# Chess_Clock_Front_Display_SCH.net
KiCad netlist of a schematic drawn in Altium Designer
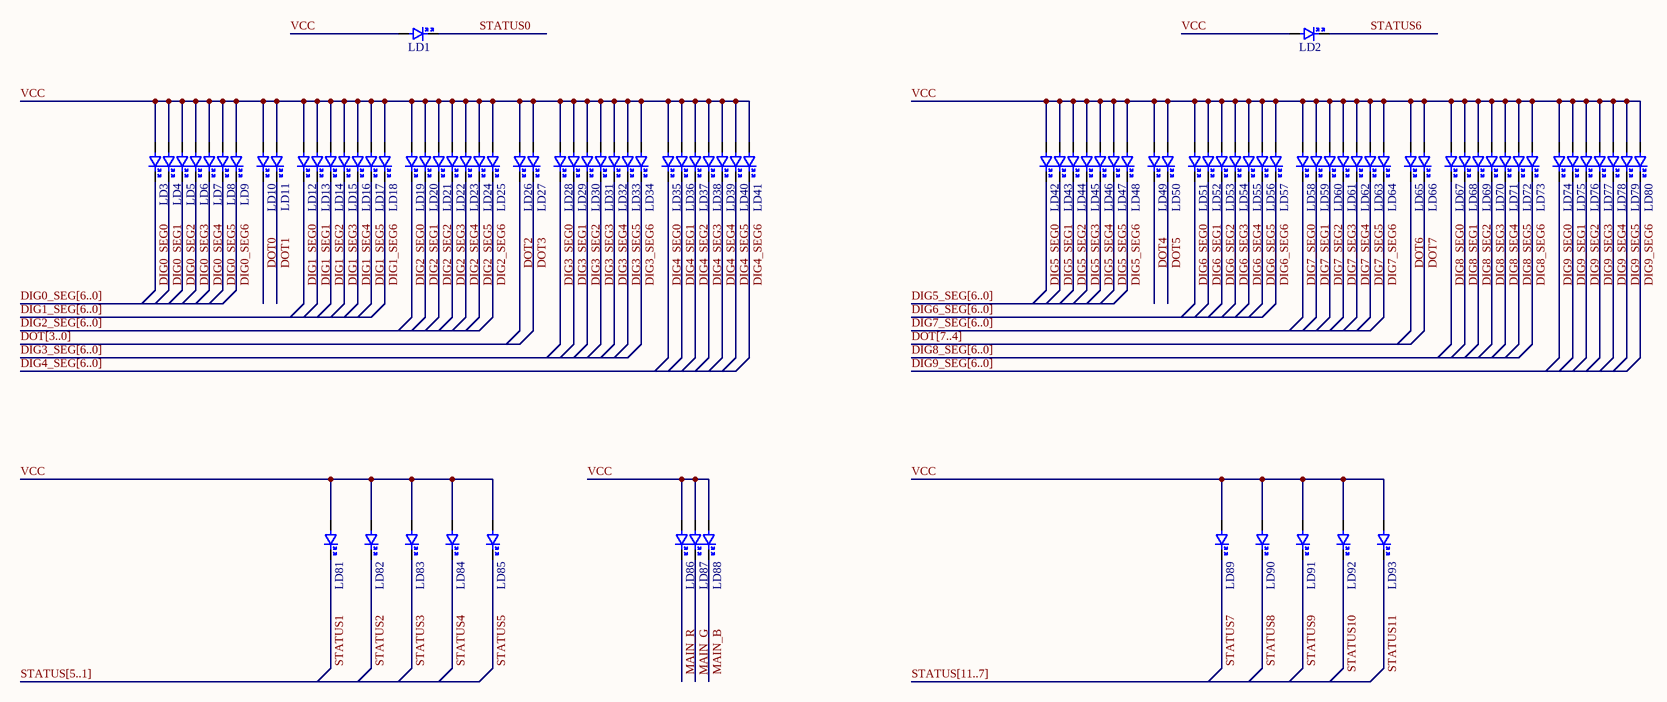
[diagram p0: Chess Clock Front Display SCH.SchDoc]

(export (version "E")
  (design (tool "Eeschema 10.0.6"))
  (components
    (comp (ref "LD1")
      (value "LED 0603")
      (footprint "LED 0603")
      (libsource (lib "Chess Clock Front Display") (part "LED 0603"))
    )
    (comp (ref "LD2")
      (value "LED 0603")
      (footprint "LED 0603")
      (libsource (lib "Chess Clock Front Display") (part "LED 0603"))
    )
    (comp (ref "LD3")
      (value "LED 0603")
      (footprint "LED 0603")
      (libsource (lib "Chess Clock Front Display") (part "LED 0603"))
    )
    (comp (ref "LD4")
      (value "LED 0603")
      (footprint "LED 0603")
      (libsource (lib "Chess Clock Front Display") (part "LED 0603"))
    )
    (comp (ref "LD5")
      (value "LED 0603")
      (footprint "LED 0603")
      (libsource (lib "Chess Clock Front Display") (part "LED 0603"))
    )
    (comp (ref "LD6")
      (value "LED 0603")
      (footprint "LED 0603")
      (libsource (lib "Chess Clock Front Display") (part "LED 0603"))
    )
    (comp (ref "LD7")
      (value "LED 0603")
      (footprint "LED 0603")
      (libsource (lib "Chess Clock Front Display") (part "LED 0603"))
    )
    (comp (ref "LD8")
      (value "LED 0603")
      (footprint "LED 0603")
      (libsource (lib "Chess Clock Front Display") (part "LED 0603"))
    )
    (comp (ref "LD9")
      (value "LED 0603")
      (footprint "LED 0603")
      (libsource (lib "Chess Clock Front Display") (part "LED 0603"))
    )
    (comp (ref "LD10")
      (value "LED 0603")
      (footprint "LED 0603")
      (libsource (lib "Chess Clock Front Display") (part "LED 0603"))
    )
    (comp (ref "LD11")
      (value "LED 0603")
      (footprint "LED 0603")
      (libsource (lib "Chess Clock Front Display") (part "LED 0603"))
    )
    (comp (ref "LD12")
      (value "LED 0603")
      (footprint "LED 0603")
      (libsource (lib "Chess Clock Front Display") (part "LED 0603"))
    )
    (comp (ref "LD13")
      (value "LED 0603")
      (footprint "LED 0603")
      (libsource (lib "Chess Clock Front Display") (part "LED 0603"))
    )
    (comp (ref "LD14")
      (value "LED 0603")
      (footprint "LED 0603")
      (libsource (lib "Chess Clock Front Display") (part "LED 0603"))
    )
    (comp (ref "LD15")
      (value "LED 0603")
      (footprint "LED 0603")
      (libsource (lib "Chess Clock Front Display") (part "LED 0603"))
    )
    (comp (ref "LD16")
      (value "LED 0603")
      (footprint "LED 0603")
      (libsource (lib "Chess Clock Front Display") (part "LED 0603"))
    )
    (comp (ref "LD17")
      (value "LED 0603")
      (footprint "LED 0603")
      (libsource (lib "Chess Clock Front Display") (part "LED 0603"))
    )
    (comp (ref "LD18")
      (value "LED 0603")
      (footprint "LED 0603")
      (libsource (lib "Chess Clock Front Display") (part "LED 0603"))
    )
    (comp (ref "LD19")
      (value "LED 0603")
      (footprint "LED 0603")
      (libsource (lib "Chess Clock Front Display") (part "LED 0603"))
    )
    (comp (ref "LD20")
      (value "LED 0603")
      (footprint "LED 0603")
      (libsource (lib "Chess Clock Front Display") (part "LED 0603"))
    )
    (comp (ref "LD21")
      (value "LED 0603")
      (footprint "LED 0603")
      (libsource (lib "Chess Clock Front Display") (part "LED 0603"))
    )
    (comp (ref "LD22")
      (value "LED 0603")
      (footprint "LED 0603")
      (libsource (lib "Chess Clock Front Display") (part "LED 0603"))
    )
    (comp (ref "LD23")
      (value "LED 0603")
      (footprint "LED 0603")
      (libsource (lib "Chess Clock Front Display") (part "LED 0603"))
    )
    (comp (ref "LD24")
      (value "LED 0603")
      (footprint "LED 0603")
      (libsource (lib "Chess Clock Front Display") (part "LED 0603"))
    )
    (comp (ref "LD25")
      (value "LED 0603")
      (footprint "LED 0603")
      (libsource (lib "Chess Clock Front Display") (part "LED 0603"))
    )
    (comp (ref "LD26")
      (value "LED 0603")
      (footprint "LED 0603")
      (libsource (lib "Chess Clock Front Display") (part "LED 0603"))
    )
    (comp (ref "LD27")
      (value "LED 0603")
      (footprint "LED 0603")
      (libsource (lib "Chess Clock Front Display") (part "LED 0603"))
    )
    (comp (ref "LD28")
      (value "LED 0603")
      (footprint "LED 0603")
      (libsource (lib "Chess Clock Front Display") (part "LED 0603"))
    )
    (comp (ref "LD29")
      (value "LED 0603")
      (footprint "LED 0603")
      (libsource (lib "Chess Clock Front Display") (part "LED 0603"))
    )
    (comp (ref "LD30")
      (value "LED 0603")
      (footprint "LED 0603")
      (libsource (lib "Chess Clock Front Display") (part "LED 0603"))
    )
    (comp (ref "LD31")
      (value "LED 0603")
      (footprint "LED 0603")
      (libsource (lib "Chess Clock Front Display") (part "LED 0603"))
    )
    (comp (ref "LD32")
      (value "LED 0603")
      (footprint "LED 0603")
      (libsource (lib "Chess Clock Front Display") (part "LED 0603"))
    )
    (comp (ref "LD33")
      (value "LED 0603")
      (footprint "LED 0603")
      (libsource (lib "Chess Clock Front Display") (part "LED 0603"))
    )
    (comp (ref "LD34")
      (value "LED 0603")
      (footprint "LED 0603")
      (libsource (lib "Chess Clock Front Display") (part "LED 0603"))
    )
    (comp (ref "LD35")
      (value "LED 0603")
      (footprint "LED 0603")
      (libsource (lib "Chess Clock Front Display") (part "LED 0603"))
    )
    (comp (ref "LD36")
      (value "LED 0603")
      (footprint "LED 0603")
      (libsource (lib "Chess Clock Front Display") (part "LED 0603"))
    )
    (comp (ref "LD37")
      (value "LED 0603")
      (footprint "LED 0603")
      (libsource (lib "Chess Clock Front Display") (part "LED 0603"))
    )
    (comp (ref "LD38")
      (value "LED 0603")
      (footprint "LED 0603")
      (libsource (lib "Chess Clock Front Display") (part "LED 0603"))
    )
    (comp (ref "LD39")
      (value "LED 0603")
      (footprint "LED 0603")
      (libsource (lib "Chess Clock Front Display") (part "LED 0603"))
    )
    (comp (ref "LD40")
      (value "LED 0603")
      (footprint "LED 0603")
      (libsource (lib "Chess Clock Front Display") (part "LED 0603"))
    )
    (comp (ref "LD41")
      (value "LED 0603")
      (footprint "LED 0603")
      (libsource (lib "Chess Clock Front Display") (part "LED 0603"))
    )
    (comp (ref "LD42")
      (value "LED 0603")
      (footprint "LED 0603")
      (libsource (lib "Chess Clock Front Display") (part "LED 0603"))
    )
    (comp (ref "LD43")
      (value "LED 0603")
      (footprint "LED 0603")
      (libsource (lib "Chess Clock Front Display") (part "LED 0603"))
    )
    (comp (ref "LD44")
      (value "LED 0603")
      (footprint "LED 0603")
      (libsource (lib "Chess Clock Front Display") (part "LED 0603"))
    )
    (comp (ref "LD45")
      (value "LED 0603")
      (footprint "LED 0603")
      (libsource (lib "Chess Clock Front Display") (part "LED 0603"))
    )
    (comp (ref "LD46")
      (value "LED 0603")
      (footprint "LED 0603")
      (libsource (lib "Chess Clock Front Display") (part "LED 0603"))
    )
    (comp (ref "LD47")
      (value "LED 0603")
      (footprint "LED 0603")
      (libsource (lib "Chess Clock Front Display") (part "LED 0603"))
    )
    (comp (ref "LD48")
      (value "LED 0603")
      (footprint "LED 0603")
      (libsource (lib "Chess Clock Front Display") (part "LED 0603"))
    )
    (comp (ref "LD49")
      (value "LED 0603")
      (footprint "LED 0603")
      (libsource (lib "Chess Clock Front Display") (part "LED 0603"))
    )
    (comp (ref "LD50")
      (value "LED 0603")
      (footprint "LED 0603")
      (libsource (lib "Chess Clock Front Display") (part "LED 0603"))
    )
    (comp (ref "LD51")
      (value "LED 0603")
      (footprint "LED 0603")
      (libsource (lib "Chess Clock Front Display") (part "LED 0603"))
    )
    (comp (ref "LD52")
      (value "LED 0603")
      (footprint "LED 0603")
      (libsource (lib "Chess Clock Front Display") (part "LED 0603"))
    )
    (comp (ref "LD53")
      (value "LED 0603")
      (footprint "LED 0603")
      (libsource (lib "Chess Clock Front Display") (part "LED 0603"))
    )
    (comp (ref "LD54")
      (value "LED 0603")
      (footprint "LED 0603")
      (libsource (lib "Chess Clock Front Display") (part "LED 0603"))
    )
    (comp (ref "LD55")
      (value "LED 0603")
      (footprint "LED 0603")
      (libsource (lib "Chess Clock Front Display") (part "LED 0603"))
    )
    (comp (ref "LD56")
      (value "LED 0603")
      (footprint "LED 0603")
      (libsource (lib "Chess Clock Front Display") (part "LED 0603"))
    )
    (comp (ref "LD57")
      (value "LED 0603")
      (footprint "LED 0603")
      (libsource (lib "Chess Clock Front Display") (part "LED 0603"))
    )
    (comp (ref "LD58")
      (value "LED 0603")
      (footprint "LED 0603")
      (libsource (lib "Chess Clock Front Display") (part "LED 0603"))
    )
    (comp (ref "LD59")
      (value "LED 0603")
      (footprint "LED 0603")
      (libsource (lib "Chess Clock Front Display") (part "LED 0603"))
    )
    (comp (ref "LD60")
      (value "LED 0603")
      (footprint "LED 0603")
      (libsource (lib "Chess Clock Front Display") (part "LED 0603"))
    )
    (comp (ref "LD61")
      (value "LED 0603")
      (footprint "LED 0603")
      (libsource (lib "Chess Clock Front Display") (part "LED 0603"))
    )
    (comp (ref "LD62")
      (value "LED 0603")
      (footprint "LED 0603")
      (libsource (lib "Chess Clock Front Display") (part "LED 0603"))
    )
    (comp (ref "LD63")
      (value "LED 0603")
      (footprint "LED 0603")
      (libsource (lib "Chess Clock Front Display") (part "LED 0603"))
    )
    (comp (ref "LD64")
      (value "LED 0603")
      (footprint "LED 0603")
      (libsource (lib "Chess Clock Front Display") (part "LED 0603"))
    )
    (comp (ref "LD65")
      (value "LED 0603")
      (footprint "LED 0603")
      (libsource (lib "Chess Clock Front Display") (part "LED 0603"))
    )
    (comp (ref "LD66")
      (value "LED 0603")
      (footprint "LED 0603")
      (libsource (lib "Chess Clock Front Display") (part "LED 0603"))
    )
    (comp (ref "LD67")
      (value "LED 0603")
      (footprint "LED 0603")
      (libsource (lib "Chess Clock Front Display") (part "LED 0603"))
    )
    (comp (ref "LD68")
      (value "LED 0603")
      (footprint "LED 0603")
      (libsource (lib "Chess Clock Front Display") (part "LED 0603"))
    )
    (comp (ref "LD69")
      (value "LED 0603")
      (footprint "LED 0603")
      (libsource (lib "Chess Clock Front Display") (part "LED 0603"))
    )
    (comp (ref "LD70")
      (value "LED 0603")
      (footprint "LED 0603")
      (libsource (lib "Chess Clock Front Display") (part "LED 0603"))
    )
    (comp (ref "LD71")
      (value "LED 0603")
      (footprint "LED 0603")
      (libsource (lib "Chess Clock Front Display") (part "LED 0603"))
    )
    (comp (ref "LD72")
      (value "LED 0603")
      (footprint "LED 0603")
      (libsource (lib "Chess Clock Front Display") (part "LED 0603"))
    )
    (comp (ref "LD73")
      (value "LED 0603")
      (footprint "LED 0603")
      (libsource (lib "Chess Clock Front Display") (part "LED 0603"))
    )
    (comp (ref "LD74")
      (value "LED 0603")
      (footprint "LED 0603")
      (libsource (lib "Chess Clock Front Display") (part "LED 0603"))
    )
    (comp (ref "LD75")
      (value "LED 0603")
      (footprint "LED 0603")
      (libsource (lib "Chess Clock Front Display") (part "LED 0603"))
    )
    (comp (ref "LD76")
      (value "LED 0603")
      (footprint "LED 0603")
      (libsource (lib "Chess Clock Front Display") (part "LED 0603"))
    )
    (comp (ref "LD77")
      (value "LED 0603")
      (footprint "LED 0603")
      (libsource (lib "Chess Clock Front Display") (part "LED 0603"))
    )
    (comp (ref "LD78")
      (value "LED 0603")
      (footprint "LED 0603")
      (libsource (lib "Chess Clock Front Display") (part "LED 0603"))
    )
    (comp (ref "LD79")
      (value "LED 0603")
      (footprint "LED 0603")
      (libsource (lib "Chess Clock Front Display") (part "LED 0603"))
    )
    (comp (ref "LD80")
      (value "LED 0603")
      (footprint "LED 0603")
      (libsource (lib "Chess Clock Front Display") (part "LED 0603"))
    )
    (comp (ref "LD81")
      (value "LED 0603")
      (footprint "LED 0603")
      (libsource (lib "Chess Clock Front Display") (part "LED 0603"))
    )
    (comp (ref "LD82")
      (value "LED 0603")
      (footprint "LED 0603")
      (libsource (lib "Chess Clock Front Display") (part "LED 0603"))
    )
    (comp (ref "LD83")
      (value "LED 0603")
      (footprint "LED 0603")
      (libsource (lib "Chess Clock Front Display") (part "LED 0603"))
    )
    (comp (ref "LD84")
      (value "LED 0603")
      (footprint "LED 0603")
      (libsource (lib "Chess Clock Front Display") (part "LED 0603"))
    )
    (comp (ref "LD85")
      (value "LED 0603")
      (footprint "LED 0603")
      (libsource (lib "Chess Clock Front Display") (part "LED 0603"))
    )
    (comp (ref "LD86")
      (value "LED 0603")
      (footprint "LED 0603")
      (libsource (lib "Chess Clock Front Display") (part "LED 0603"))
    )
    (comp (ref "LD87")
      (value "LED 0603")
      (footprint "LED 0603")
      (libsource (lib "Chess Clock Front Display") (part "LED 0603"))
    )
    (comp (ref "LD88")
      (value "LED 0603")
      (footprint "LED 0603")
      (libsource (lib "Chess Clock Front Display") (part "LED 0603"))
    )
    (comp (ref "LD89")
      (value "LED 0603")
      (footprint "LED 0603")
      (libsource (lib "Chess Clock Front Display") (part "LED 0603"))
    )
    (comp (ref "LD90")
      (value "LED 0603")
      (footprint "LED 0603")
      (libsource (lib "Chess Clock Front Display") (part "LED 0603"))
    )
    (comp (ref "LD91")
      (value "LED 0603")
      (footprint "LED 0603")
      (libsource (lib "Chess Clock Front Display") (part "LED 0603"))
    )
    (comp (ref "LD92")
      (value "LED 0603")
      (footprint "LED 0603")
      (libsource (lib "Chess Clock Front Display") (part "LED 0603"))
    )
    (comp (ref "LD93")
      (value "LED 0603")
      (footprint "LED 0603")
      (libsource (lib "Chess Clock Front Display") (part "LED 0603"))
    )
  )
  (nets
    (net (code "1") (name "/DIG0_SEG0") (class "Default")
      (node (ref "LD3") (pin "2") (pinfunction "2_2") (pintype "passive"))
    )
    (net (code "2") (name "/DIG0_SEG1") (class "Default")
      (node (ref "LD4") (pin "2") (pinfunction "2_2") (pintype "passive"))
    )
    (net (code "3") (name "/DIG0_SEG2") (class "Default")
      (node (ref "LD5") (pin "2") (pinfunction "2_2") (pintype "passive"))
    )
    (net (code "4") (name "/DIG0_SEG3") (class "Default")
      (node (ref "LD6") (pin "2") (pinfunction "2_2") (pintype "passive"))
    )
    (net (code "5") (name "/DIG0_SEG4") (class "Default")
      (node (ref "LD7") (pin "2") (pinfunction "2_2") (pintype "passive"))
    )
    (net (code "6") (name "/DIG0_SEG5") (class "Default")
      (node (ref "LD8") (pin "2") (pinfunction "2_2") (pintype "passive"))
    )
    (net (code "7") (name "/DIG0_SEG6") (class "Default")
      (node (ref "LD9") (pin "2") (pinfunction "2_2") (pintype "passive"))
    )
    (net (code "9") (name "/DIG1_SEG0") (class "Default")
      (node (ref "LD12") (pin "2") (pinfunction "2_2") (pintype "passive"))
    )
    (net (code "10") (name "/DIG1_SEG1") (class "Default")
      (node (ref "LD13") (pin "2") (pinfunction "2_2") (pintype "passive"))
    )
    (net (code "11") (name "/DIG1_SEG2") (class "Default")
      (node (ref "LD14") (pin "2") (pinfunction "2_2") (pintype "passive"))
    )
    (net (code "12") (name "/DIG1_SEG3") (class "Default")
      (node (ref "LD15") (pin "2") (pinfunction "2_2") (pintype "passive"))
    )
    (net (code "13") (name "/DIG1_SEG4") (class "Default")
      (node (ref "LD16") (pin "2") (pinfunction "2_2") (pintype "passive"))
    )
    (net (code "14") (name "/DIG1_SEG5") (class "Default")
      (node (ref "LD17") (pin "2") (pinfunction "2_2") (pintype "passive"))
    )
    (net (code "15") (name "/DIG1_SEG6") (class "Default")
      (node (ref "LD18") (pin "2") (pinfunction "2_2") (pintype "passive"))
    )
    (net (code "17") (name "/DIG2_SEG0") (class "Default")
      (node (ref "LD19") (pin "2") (pinfunction "2_2") (pintype "passive"))
    )
    (net (code "18") (name "/DIG2_SEG1") (class "Default")
      (node (ref "LD20") (pin "2") (pinfunction "2_2") (pintype "passive"))
    )
    (net (code "19") (name "/DIG2_SEG2") (class "Default")
      (node (ref "LD21") (pin "2") (pinfunction "2_2") (pintype "passive"))
    )
    (net (code "20") (name "/DIG2_SEG3") (class "Default")
      (node (ref "LD22") (pin "2") (pinfunction "2_2") (pintype "passive"))
    )
    (net (code "21") (name "/DIG2_SEG4") (class "Default")
      (node (ref "LD23") (pin "2") (pinfunction "2_2") (pintype "passive"))
    )
    (net (code "22") (name "/DIG2_SEG5") (class "Default")
      (node (ref "LD24") (pin "2") (pinfunction "2_2") (pintype "passive"))
    )
    (net (code "23") (name "/DIG2_SEG6") (class "Default")
      (node (ref "LD25") (pin "2") (pinfunction "2_2") (pintype "passive"))
    )
    (net (code "25") (name "/DIG3_SEG0") (class "Default")
      (node (ref "LD28") (pin "2") (pinfunction "2_2") (pintype "passive"))
    )
    (net (code "26") (name "/DIG3_SEG1") (class "Default")
      (node (ref "LD29") (pin "2") (pinfunction "2_2") (pintype "passive"))
    )
    (net (code "27") (name "/DIG3_SEG2") (class "Default")
      (node (ref "LD30") (pin "2") (pinfunction "2_2") (pintype "passive"))
    )
    (net (code "28") (name "/DIG3_SEG3") (class "Default")
      (node (ref "LD31") (pin "2") (pinfunction "2_2") (pintype "passive"))
    )
    (net (code "29") (name "/DIG3_SEG4") (class "Default")
      (node (ref "LD32") (pin "2") (pinfunction "2_2") (pintype "passive"))
    )
    (net (code "30") (name "/DIG3_SEG5") (class "Default")
      (node (ref "LD33") (pin "2") (pinfunction "2_2") (pintype "passive"))
    )
    (net (code "31") (name "/DIG3_SEG6") (class "Default")
      (node (ref "LD34") (pin "2") (pinfunction "2_2") (pintype "passive"))
    )
    (net (code "33") (name "/DIG4_SEG0") (class "Default")
      (node (ref "LD35") (pin "2") (pinfunction "2_2") (pintype "passive"))
    )
    (net (code "34") (name "/DIG4_SEG1") (class "Default")
      (node (ref "LD36") (pin "2") (pinfunction "2_2") (pintype "passive"))
    )
    (net (code "35") (name "/DIG4_SEG2") (class "Default")
      (node (ref "LD37") (pin "2") (pinfunction "2_2") (pintype "passive"))
    )
    (net (code "36") (name "/DIG4_SEG3") (class "Default")
      (node (ref "LD38") (pin "2") (pinfunction "2_2") (pintype "passive"))
    )
    (net (code "37") (name "/DIG4_SEG4") (class "Default")
      (node (ref "LD39") (pin "2") (pinfunction "2_2") (pintype "passive"))
    )
    (net (code "38") (name "/DIG4_SEG5") (class "Default")
      (node (ref "LD40") (pin "2") (pinfunction "2_2") (pintype "passive"))
    )
    (net (code "39") (name "/DIG4_SEG6") (class "Default")
      (node (ref "LD41") (pin "2") (pinfunction "2_2") (pintype "passive"))
    )
    (net (code "41") (name "/DIG5_SEG0") (class "Default")
      (node (ref "LD42") (pin "2") (pinfunction "2_2") (pintype "passive"))
    )
    (net (code "42") (name "/DIG5_SEG1") (class "Default")
      (node (ref "LD43") (pin "2") (pinfunction "2_2") (pintype "passive"))
    )
    (net (code "43") (name "/DIG5_SEG2") (class "Default")
      (node (ref "LD44") (pin "2") (pinfunction "2_2") (pintype "passive"))
    )
    (net (code "44") (name "/DIG5_SEG3") (class "Default")
      (node (ref "LD45") (pin "2") (pinfunction "2_2") (pintype "passive"))
    )
    (net (code "45") (name "/DIG5_SEG4") (class "Default")
      (node (ref "LD46") (pin "2") (pinfunction "2_2") (pintype "passive"))
    )
    (net (code "46") (name "/DIG5_SEG5") (class "Default")
      (node (ref "LD47") (pin "2") (pinfunction "2_2") (pintype "passive"))
    )
    (net (code "47") (name "/DIG5_SEG6") (class "Default")
      (node (ref "LD48") (pin "2") (pinfunction "2_2") (pintype "passive"))
    )
    (net (code "49") (name "/DIG6_SEG0") (class "Default")
      (node (ref "LD51") (pin "2") (pinfunction "2_2") (pintype "passive"))
    )
    (net (code "50") (name "/DIG6_SEG1") (class "Default")
      (node (ref "LD52") (pin "2") (pinfunction "2_2") (pintype "passive"))
    )
    (net (code "51") (name "/DIG6_SEG2") (class "Default")
      (node (ref "LD53") (pin "2") (pinfunction "2_2") (pintype "passive"))
    )
    (net (code "52") (name "/DIG6_SEG3") (class "Default")
      (node (ref "LD54") (pin "2") (pinfunction "2_2") (pintype "passive"))
    )
    (net (code "53") (name "/DIG6_SEG4") (class "Default")
      (node (ref "LD55") (pin "2") (pinfunction "2_2") (pintype "passive"))
    )
    (net (code "54") (name "/DIG6_SEG5") (class "Default")
      (node (ref "LD56") (pin "2") (pinfunction "2_2") (pintype "passive"))
    )
    (net (code "55") (name "/DIG6_SEG6") (class "Default")
      (node (ref "LD57") (pin "2") (pinfunction "2_2") (pintype "passive"))
    )
    (net (code "57") (name "/DIG7_SEG0") (class "Default")
      (node (ref "LD58") (pin "2") (pinfunction "2_2") (pintype "passive"))
    )
    (net (code "58") (name "/DIG7_SEG1") (class "Default")
      (node (ref "LD59") (pin "2") (pinfunction "2_2") (pintype "passive"))
    )
    (net (code "59") (name "/DIG7_SEG2") (class "Default")
      (node (ref "LD60") (pin "2") (pinfunction "2_2") (pintype "passive"))
    )
    (net (code "60") (name "/DIG7_SEG3") (class "Default")
      (node (ref "LD61") (pin "2") (pinfunction "2_2") (pintype "passive"))
    )
    (net (code "61") (name "/DIG7_SEG4") (class "Default")
      (node (ref "LD62") (pin "2") (pinfunction "2_2") (pintype "passive"))
    )
    (net (code "62") (name "/DIG7_SEG5") (class "Default")
      (node (ref "LD63") (pin "2") (pinfunction "2_2") (pintype "passive"))
    )
    (net (code "63") (name "/DIG7_SEG6") (class "Default")
      (node (ref "LD64") (pin "2") (pinfunction "2_2") (pintype "passive"))
    )
    (net (code "65") (name "/DIG8_SEG0") (class "Default")
      (node (ref "LD67") (pin "2") (pinfunction "2_2") (pintype "passive"))
    )
    (net (code "66") (name "/DIG8_SEG1") (class "Default")
      (node (ref "LD68") (pin "2") (pinfunction "2_2") (pintype "passive"))
    )
    (net (code "67") (name "/DIG8_SEG2") (class "Default")
      (node (ref "LD69") (pin "2") (pinfunction "2_2") (pintype "passive"))
    )
    (net (code "68") (name "/DIG8_SEG3") (class "Default")
      (node (ref "LD70") (pin "2") (pinfunction "2_2") (pintype "passive"))
    )
    (net (code "69") (name "/DIG8_SEG4") (class "Default")
      (node (ref "LD71") (pin "2") (pinfunction "2_2") (pintype "passive"))
    )
    (net (code "70") (name "/DIG8_SEG5") (class "Default")
      (node (ref "LD72") (pin "2") (pinfunction "2_2") (pintype "passive"))
    )
    (net (code "71") (name "/DIG8_SEG6") (class "Default")
      (node (ref "LD73") (pin "2") (pinfunction "2_2") (pintype "passive"))
    )
    (net (code "73") (name "/DIG9_SEG0") (class "Default")
      (node (ref "LD74") (pin "2") (pinfunction "2_2") (pintype "passive"))
    )
    (net (code "74") (name "/DIG9_SEG1") (class "Default")
      (node (ref "LD75") (pin "2") (pinfunction "2_2") (pintype "passive"))
    )
    (net (code "75") (name "/DIG9_SEG2") (class "Default")
      (node (ref "LD76") (pin "2") (pinfunction "2_2") (pintype "passive"))
    )
    (net (code "76") (name "/DIG9_SEG3") (class "Default")
      (node (ref "LD77") (pin "2") (pinfunction "2_2") (pintype "passive"))
    )
    (net (code "77") (name "/DIG9_SEG4") (class "Default")
      (node (ref "LD78") (pin "2") (pinfunction "2_2") (pintype "passive"))
    )
    (net (code "78") (name "/DIG9_SEG5") (class "Default")
      (node (ref "LD79") (pin "2") (pinfunction "2_2") (pintype "passive"))
    )
    (net (code "79") (name "/DIG9_SEG6") (class "Default")
      (node (ref "LD80") (pin "2") (pinfunction "2_2") (pintype "passive"))
    )
    (net (code "81") (name "/DOT0") (class "Default")
      (node (ref "LD10") (pin "2") (pinfunction "2_2") (pintype "passive"))
    )
    (net (code "82") (name "/DOT1") (class "Default")
      (node (ref "LD11") (pin "2") (pinfunction "2_2") (pintype "passive"))
    )
    (net (code "83") (name "/DOT2") (class "Default")
      (node (ref "LD26") (pin "2") (pinfunction "2_2") (pintype "passive"))
    )
    (net (code "84") (name "/DOT3") (class "Default")
      (node (ref "LD27") (pin "2") (pinfunction "2_2") (pintype "passive"))
    )
    (net (code "85") (name "/DOT4") (class "Default")
      (node (ref "LD49") (pin "2") (pinfunction "2_2") (pintype "passive"))
    )
    (net (code "86") (name "/DOT5") (class "Default")
      (node (ref "LD50") (pin "2") (pinfunction "2_2") (pintype "passive"))
    )
    (net (code "87") (name "/DOT6") (class "Default")
      (node (ref "LD65") (pin "2") (pinfunction "2_2") (pintype "passive"))
    )
    (net (code "88") (name "/DOT7") (class "Default")
      (node (ref "LD66") (pin "2") (pinfunction "2_2") (pintype "passive"))
    )
    (net (code "91") (name "/MAIN_B") (class "Default")
      (node (ref "LD88") (pin "2") (pinfunction "2_2") (pintype "passive"))
    )
    (net (code "92") (name "/MAIN_G") (class "Default")
      (node (ref "LD87") (pin "2") (pinfunction "2_2") (pintype "passive"))
    )
    (net (code "93") (name "/MAIN_R") (class "Default")
      (node (ref "LD86") (pin "2") (pinfunction "2_2") (pintype "passive"))
    )
    (net (code "94") (name "/STATUS0") (class "Default")
      (node (ref "LD1") (pin "2") (pinfunction "2_2") (pintype "passive"))
    )
    (net (code "95") (name "/STATUS1") (class "Default")
      (node (ref "LD81") (pin "2") (pinfunction "2_2") (pintype "passive"))
    )
    (net (code "96") (name "/STATUS2") (class "Default")
      (node (ref "LD82") (pin "2") (pinfunction "2_2") (pintype "passive"))
    )
    (net (code "97") (name "/STATUS3") (class "Default")
      (node (ref "LD83") (pin "2") (pinfunction "2_2") (pintype "passive"))
    )
    (net (code "98") (name "/STATUS4") (class "Default")
      (node (ref "LD84") (pin "2") (pinfunction "2_2") (pintype "passive"))
    )
    (net (code "99") (name "/STATUS5") (class "Default")
      (node (ref "LD85") (pin "2") (pinfunction "2_2") (pintype "passive"))
    )
    (net (code "100") (name "/STATUS6") (class "Default")
      (node (ref "LD2") (pin "2") (pinfunction "2_2") (pintype "passive"))
    )
    (net (code "101") (name "/STATUS7") (class "Default")
      (node (ref "LD89") (pin "2") (pinfunction "2_2") (pintype "passive"))
    )
    (net (code "102") (name "/STATUS8") (class "Default")
      (node (ref "LD90") (pin "2") (pinfunction "2_2") (pintype "passive"))
    )
    (net (code "103") (name "/STATUS9") (class "Default")
      (node (ref "LD91") (pin "2") (pinfunction "2_2") (pintype "passive"))
    )
    (net (code "104") (name "/STATUS10") (class "Default")
      (node (ref "LD92") (pin "2") (pinfunction "2_2") (pintype "passive"))
    )
    (net (code "105") (name "/STATUS11") (class "Default")
      (node (ref "LD93") (pin "2") (pinfunction "2_2") (pintype "passive"))
    )
    (net (code "108") (name "/VCC") (class "Default")
      (node (ref "LD1") (pin "1") (pinfunction "1_1") (pintype "passive"))
      (node (ref "LD10") (pin "1") (pinfunction "1_1") (pintype "passive"))
      (node (ref "LD11") (pin "1") (pinfunction "1_1") (pintype "passive"))
      (node (ref "LD12") (pin "1") (pinfunction "1_1") (pintype "passive"))
      (node (ref "LD13") (pin "1") (pinfunction "1_1") (pintype "passive"))
      (node (ref "LD14") (pin "1") (pinfunction "1_1") (pintype "passive"))
      (node (ref "LD15") (pin "1") (pinfunction "1_1") (pintype "passive"))
      (node (ref "LD16") (pin "1") (pinfunction "1_1") (pintype "passive"))
      (node (ref "LD17") (pin "1") (pinfunction "1_1") (pintype "passive"))
      (node (ref "LD18") (pin "1") (pinfunction "1_1") (pintype "passive"))
      (node (ref "LD19") (pin "1") (pinfunction "1_1") (pintype "passive"))
      (node (ref "LD2") (pin "1") (pinfunction "1_1") (pintype "passive"))
      (node (ref "LD20") (pin "1") (pinfunction "1_1") (pintype "passive"))
      (node (ref "LD21") (pin "1") (pinfunction "1_1") (pintype "passive"))
      (node (ref "LD22") (pin "1") (pinfunction "1_1") (pintype "passive"))
      (node (ref "LD23") (pin "1") (pinfunction "1_1") (pintype "passive"))
      (node (ref "LD24") (pin "1") (pinfunction "1_1") (pintype "passive"))
      (node (ref "LD25") (pin "1") (pinfunction "1_1") (pintype "passive"))
      (node (ref "LD26") (pin "1") (pinfunction "1_1") (pintype "passive"))
      (node (ref "LD27") (pin "1") (pinfunction "1_1") (pintype "passive"))
      (node (ref "LD28") (pin "1") (pinfunction "1_1") (pintype "passive"))
      (node (ref "LD29") (pin "1") (pinfunction "1_1") (pintype "passive"))
      (node (ref "LD3") (pin "1") (pinfunction "1_1") (pintype "passive"))
      (node (ref "LD30") (pin "1") (pinfunction "1_1") (pintype "passive"))
      (node (ref "LD31") (pin "1") (pinfunction "1_1") (pintype "passive"))
      (node (ref "LD32") (pin "1") (pinfunction "1_1") (pintype "passive"))
      (node (ref "LD33") (pin "1") (pinfunction "1_1") (pintype "passive"))
      (node (ref "LD34") (pin "1") (pinfunction "1_1") (pintype "passive"))
      (node (ref "LD35") (pin "1") (pinfunction "1_1") (pintype "passive"))
      (node (ref "LD36") (pin "1") (pinfunction "1_1") (pintype "passive"))
      (node (ref "LD37") (pin "1") (pinfunction "1_1") (pintype "passive"))
      (node (ref "LD38") (pin "1") (pinfunction "1_1") (pintype "passive"))
      (node (ref "LD39") (pin "1") (pinfunction "1_1") (pintype "passive"))
      (node (ref "LD4") (pin "1") (pinfunction "1_1") (pintype "passive"))
      (node (ref "LD40") (pin "1") (pinfunction "1_1") (pintype "passive"))
      (node (ref "LD41") (pin "1") (pinfunction "1_1") (pintype "passive"))
      (node (ref "LD42") (pin "1") (pinfunction "1_1") (pintype "passive"))
      (node (ref "LD43") (pin "1") (pinfunction "1_1") (pintype "passive"))
      (node (ref "LD44") (pin "1") (pinfunction "1_1") (pintype "passive"))
      (node (ref "LD45") (pin "1") (pinfunction "1_1") (pintype "passive"))
      (node (ref "LD46") (pin "1") (pinfunction "1_1") (pintype "passive"))
      (node (ref "LD47") (pin "1") (pinfunction "1_1") (pintype "passive"))
      (node (ref "LD48") (pin "1") (pinfunction "1_1") (pintype "passive"))
      (node (ref "LD49") (pin "1") (pinfunction "1_1") (pintype "passive"))
      (node (ref "LD5") (pin "1") (pinfunction "1_1") (pintype "passive"))
      (node (ref "LD50") (pin "1") (pinfunction "1_1") (pintype "passive"))
      (node (ref "LD51") (pin "1") (pinfunction "1_1") (pintype "passive"))
      (node (ref "LD52") (pin "1") (pinfunction "1_1") (pintype "passive"))
      (node (ref "LD53") (pin "1") (pinfunction "1_1") (pintype "passive"))
      (node (ref "LD54") (pin "1") (pinfunction "1_1") (pintype "passive"))
      (node (ref "LD55") (pin "1") (pinfunction "1_1") (pintype "passive"))
      (node (ref "LD56") (pin "1") (pinfunction "1_1") (pintype "passive"))
      (node (ref "LD57") (pin "1") (pinfunction "1_1") (pintype "passive"))
      (node (ref "LD58") (pin "1") (pinfunction "1_1") (pintype "passive"))
      (node (ref "LD59") (pin "1") (pinfunction "1_1") (pintype "passive"))
      (node (ref "LD6") (pin "1") (pinfunction "1_1") (pintype "passive"))
      (node (ref "LD60") (pin "1") (pinfunction "1_1") (pintype "passive"))
      (node (ref "LD61") (pin "1") (pinfunction "1_1") (pintype "passive"))
      (node (ref "LD62") (pin "1") (pinfunction "1_1") (pintype "passive"))
      (node (ref "LD63") (pin "1") (pinfunction "1_1") (pintype "passive"))
      (node (ref "LD64") (pin "1") (pinfunction "1_1") (pintype "passive"))
      (node (ref "LD65") (pin "1") (pinfunction "1_1") (pintype "passive"))
      (node (ref "LD66") (pin "1") (pinfunction "1_1") (pintype "passive"))
      (node (ref "LD67") (pin "1") (pinfunction "1_1") (pintype "passive"))
      (node (ref "LD68") (pin "1") (pinfunction "1_1") (pintype "passive"))
      (node (ref "LD69") (pin "1") (pinfunction "1_1") (pintype "passive"))
      (node (ref "LD7") (pin "1") (pinfunction "1_1") (pintype "passive"))
      (node (ref "LD70") (pin "1") (pinfunction "1_1") (pintype "passive"))
      (node (ref "LD71") (pin "1") (pinfunction "1_1") (pintype "passive"))
      (node (ref "LD72") (pin "1") (pinfunction "1_1") (pintype "passive"))
      (node (ref "LD73") (pin "1") (pinfunction "1_1") (pintype "passive"))
      (node (ref "LD74") (pin "1") (pinfunction "1_1") (pintype "passive"))
      (node (ref "LD75") (pin "1") (pinfunction "1_1") (pintype "passive"))
      (node (ref "LD76") (pin "1") (pinfunction "1_1") (pintype "passive"))
      (node (ref "LD77") (pin "1") (pinfunction "1_1") (pintype "passive"))
      (node (ref "LD78") (pin "1") (pinfunction "1_1") (pintype "passive"))
      (node (ref "LD79") (pin "1") (pinfunction "1_1") (pintype "passive"))
      (node (ref "LD8") (pin "1") (pinfunction "1_1") (pintype "passive"))
      (node (ref "LD80") (pin "1") (pinfunction "1_1") (pintype "passive"))
      (node (ref "LD81") (pin "1") (pinfunction "1_1") (pintype "passive"))
      (node (ref "LD82") (pin "1") (pinfunction "1_1") (pintype "passive"))
      (node (ref "LD83") (pin "1") (pinfunction "1_1") (pintype "passive"))
      (node (ref "LD84") (pin "1") (pinfunction "1_1") (pintype "passive"))
      (node (ref "LD85") (pin "1") (pinfunction "1_1") (pintype "passive"))
      (node (ref "LD86") (pin "1") (pinfunction "1_1") (pintype "passive"))
      (node (ref "LD87") (pin "1") (pinfunction "1_1") (pintype "passive"))
      (node (ref "LD88") (pin "1") (pinfunction "1_1") (pintype "passive"))
      (node (ref "LD89") (pin "1") (pinfunction "1_1") (pintype "passive"))
      (node (ref "LD9") (pin "1") (pinfunction "1_1") (pintype "passive"))
      (node (ref "LD90") (pin "1") (pinfunction "1_1") (pintype "passive"))
      (node (ref "LD91") (pin "1") (pinfunction "1_1") (pintype "passive"))
      (node (ref "LD92") (pin "1") (pinfunction "1_1") (pintype "passive"))
      (node (ref "LD93") (pin "1") (pinfunction "1_1") (pintype "passive"))
    )
  )
)
